# pure_energy.net
KiCad netlist of a schematic drawn in EAGLE
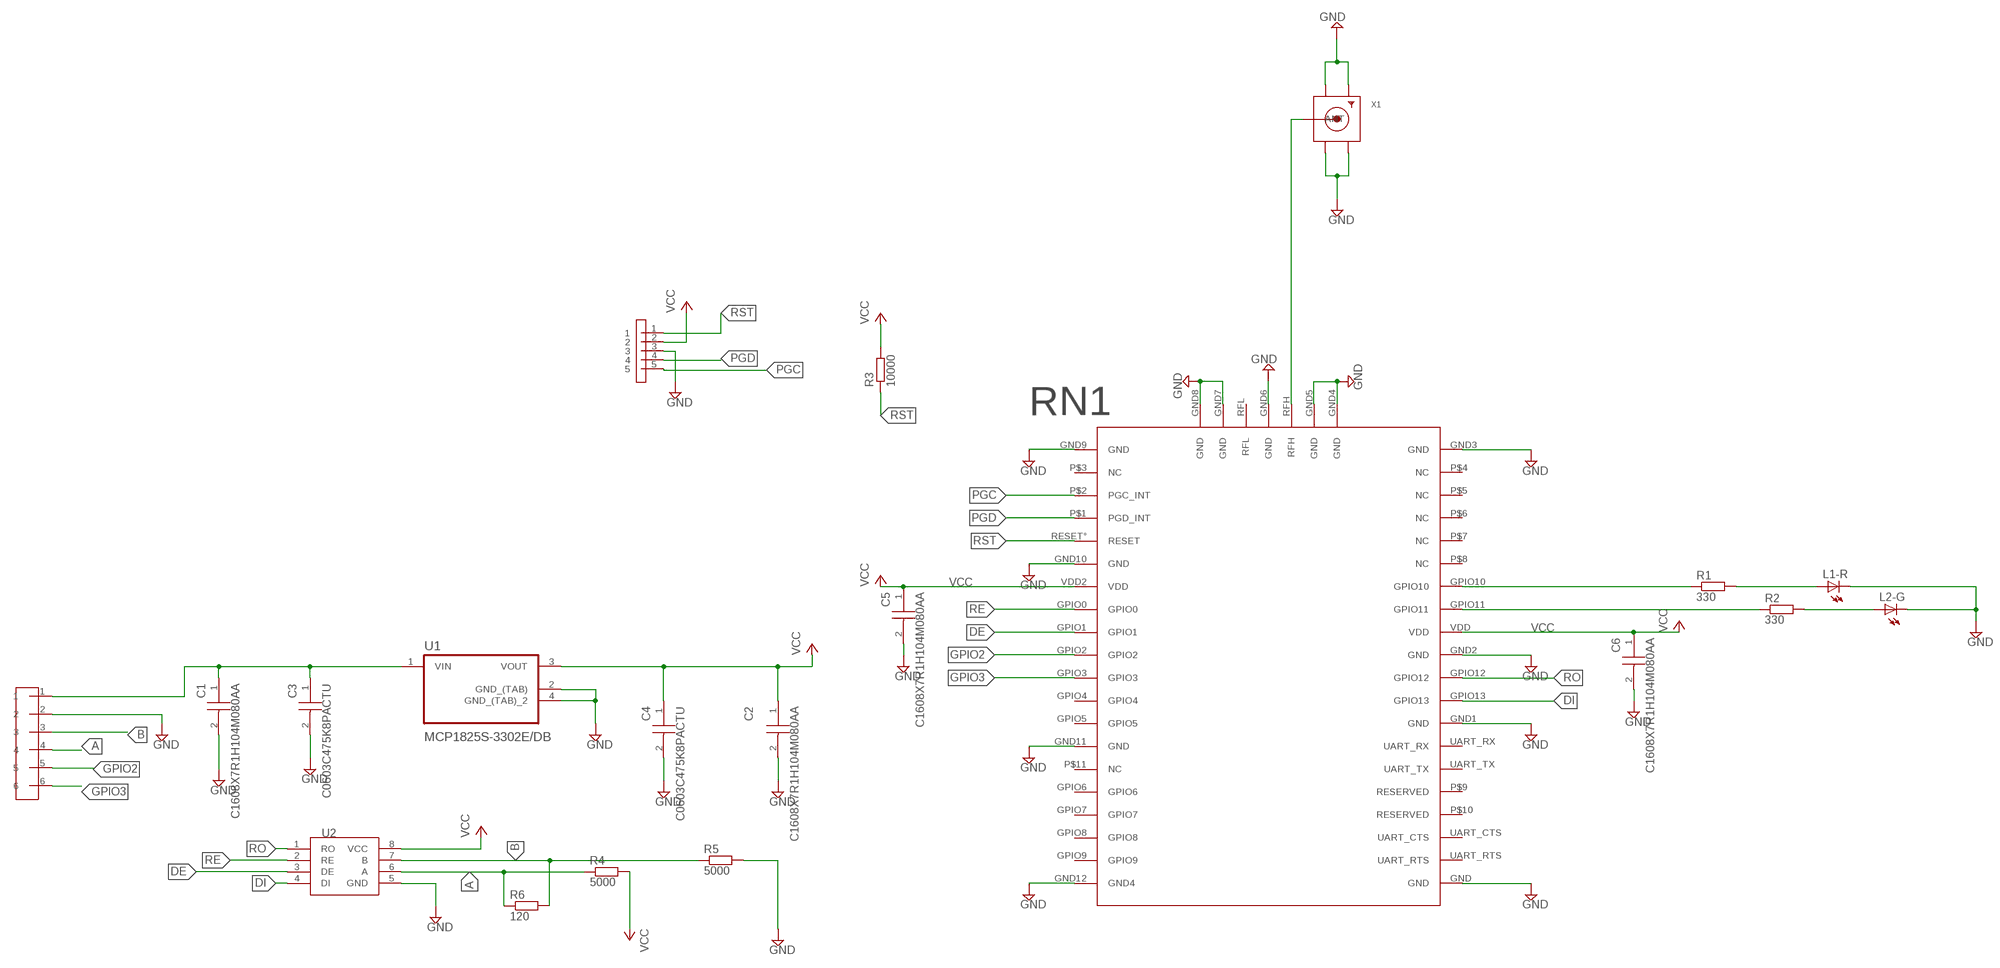
[diagram p0: schematic, sheet 1]

(export (version "E")
  (design (tool "Eeschema 10.0.6"))
  (components
    (comp (ref "C1")
      (value "C1608X7R1H104M080AA")
      (footprint "eagle-import:CAPC1608X80N")
      (fields (field (name "MOUSER_PART_NUMBER") "810-C1608X7R1H104M"))
      (libsource (lib "eagle-import") (part "C1608X7R1H104M080AA"))
    )
    (comp (ref "C2")
      (value "C1608X7R1H104M080AA")
      (footprint "eagle-import:CAPC1608X80N")
      (fields (field (name "MOUSER_PART_NUMBER") "810-C1608X7R1H104M"))
      (libsource (lib "eagle-import") (part "C1608X7R1H104M080AA"))
    )
    (comp (ref "C3")
      (value "C0603C475K8PACTU")
      (footprint "eagle-import:CAPC1608X85N")
      (fields (field (name "MOUSER_PART_NUMBER") "80-C0603C475K8P"))
      (libsource (lib "eagle-import") (part "C0603C475K8PACTU"))
    )
    (comp (ref "C4")
      (value "C0603C475K8PACTU")
      (footprint "eagle-import:CAPC1608X85N")
      (fields (field (name "MOUSER_PART_NUMBER") "80-C0603C475K8P"))
      (libsource (lib "eagle-import") (part "C0603C475K8PACTU"))
    )
    (comp (ref "C5")
      (value "C1608X7R1H104M080AA")
      (footprint "eagle-import:CAPC1608X80N")
      (fields (field (name "MOUSER_PART_NUMBER") "810-C1608X7R1H104M"))
      (libsource (lib "eagle-import") (part "C1608X7R1H104M080AA"))
    )
    (comp (ref "C6")
      (value "C1608X7R1H104M080AA")
      (footprint "eagle-import:CAPC1608X80N")
      (fields (field (name "MOUSER_PART_NUMBER") "810-C1608X7R1H104M"))
      (libsource (lib "eagle-import") (part "C1608X7R1H104M080AA"))
    )
    (comp (ref "L1-R")
      (value "LEDCHIP-LED0603")
      (footprint "eagle-import:CHIP-LED0603")
      (libsource (lib "eagle-import") (part "LEDCHIP-LED0603"))
    )
    (comp (ref "L2-G")
      (value "LEDCHIP-LED0603")
      (footprint "eagle-import:CHIP-LED0603")
      (libsource (lib "eagle-import") (part "LEDCHIP-LED0603"))
    )
    (comp (ref "R1")
      (value "330")
      (footprint "eagle-import:R0603")
      (libsource (lib "eagle-import") (part "R-EU_R0603"))
    )
    (comp (ref "R2")
      (value "330")
      (footprint "eagle-import:R0603")
      (libsource (lib "eagle-import") (part "R-EU_R0603"))
    )
    (comp (ref "R3")
      (value "10000")
      (footprint "eagle-import:R0603")
      (libsource (lib "eagle-import") (part "R-EU_R0603"))
    )
    (comp (ref "R4")
      (value "5000")
      (footprint "eagle-import:R0805")
      (libsource (lib "eagle-import") (part "R-EU_R0805"))
    )
    (comp (ref "R5")
      (value "5000")
      (footprint "eagle-import:R0805")
      (libsource (lib "eagle-import") (part "R-EU_R0805"))
    )
    (comp (ref "R6")
      (value "120")
      (footprint "eagle-import:R0805")
      (libsource (lib "eagle-import") (part "R-EU_R0805"))
    )
    (comp (ref "RN1")
      (value "NEW_RN2483")
      (footprint "eagle-import:NEW_RN2483")
      (libsource (lib "eagle-import") (part "NEW_RN2483"))
    )
    (comp (ref "U$1")
      (value "CONNECTOR6_V2")
      (footprint "eagle-import:CONNECTOR6_V2")
      (libsource (lib "eagle-import") (part "CONNECTOR6_V2"))
    )
    (comp (ref "U$3")
      (value "ICSP_V2")
      (footprint "eagle-import:ICSP_V2")
      (libsource (lib "eagle-import") (part "ICSP_V2"))
    )
    (comp (ref "U1")
      (value "MCP1825S-3302E/DB")
      (footprint "eagle-import:SOT230P700X180-4N")
      (fields (field (name "MF") "Microchip"))
      (libsource (lib "eagle-import") (part "MCP1825S-3302E/DB"))
    )
    (comp (ref "U2")
      (value "AMD3485E")
      (footprint "eagle-import:AMD3485E")
      (libsource (lib "eagle-import") (part "AMD3485E"))
    )
    (comp (ref "X1")
      (value "SMACONNECTOR_EDGE")
      (footprint "eagle-import:SMA_EDGELAUNCH")
      (libsource (lib "eagle-import") (part "SMACONNECTOR_EDGE"))
    )
  )
  (nets
    (net (code "1") (name "A") (class "Default")
      (node (ref "R4") (pin "1") (pinfunction "1_1") (pintype "passive"))
      (node (ref "R6") (pin "1") (pinfunction "1_1") (pintype "passive"))
      (node (ref "U$1") (pin "4") (pinfunction "4_4") (pintype "bidirectional"))
      (node (ref "U2") (pin "6") (pinfunction "A_6") (pintype "bidirectional"))
    )
    (net (code "2") (name "B") (class "Default")
      (node (ref "R5") (pin "1") (pinfunction "1_1") (pintype "passive"))
      (node (ref "R6") (pin "2") (pinfunction "2_2") (pintype "passive"))
      (node (ref "U$1") (pin "3") (pinfunction "3_3") (pintype "bidirectional"))
      (node (ref "U2") (pin "7") (pinfunction "B_7") (pintype "bidirectional"))
    )
    (net (code "3") (name "DE") (class "Default")
      (node (ref "RN1") (pin "GPIO1") (pinfunction "GPIO1_GPIO1") (pintype "bidirectional"))
      (node (ref "U2") (pin "3") (pinfunction "DE_3") (pintype "bidirectional"))
    )
    (net (code "4") (name "DI") (class "Default")
      (node (ref "RN1") (pin "GPIO13") (pinfunction "GPIO13_GPIO13") (pintype "bidirectional"))
      (node (ref "U2") (pin "4") (pinfunction "DI_4") (pintype "bidirectional"))
    )
    (net (code "5") (name "GND") (class "Default")
      (node (ref "C1") (pin "2") (pinfunction "2_2") (pintype "bidirectional"))
      (node (ref "C2") (pin "2") (pinfunction "2_2") (pintype "bidirectional"))
      (node (ref "C3") (pin "2") (pinfunction "C2_2") (pintype "bidirectional"))
      (node (ref "C4") (pin "2") (pinfunction "C2_2") (pintype "bidirectional"))
      (node (ref "C5") (pin "2") (pinfunction "2_2") (pintype "bidirectional"))
      (node (ref "C6") (pin "2") (pinfunction "2_2") (pintype "bidirectional"))
      (node (ref "L1-R") (pin "C") (pinfunction "C_C") (pintype "passive"))
      (node (ref "L2-G") (pin "C") (pinfunction "C_C") (pintype "passive"))
      (node (ref "R5") (pin "2") (pinfunction "2_2") (pintype "passive"))
      (node (ref "RN1") (pin "GND") (pinfunction "GND_GND") (pintype "bidirectional"))
      (node (ref "RN1") (pin "GND1") (pinfunction "GND_GND1") (pintype "bidirectional"))
      (node (ref "RN1") (pin "GND10") (pinfunction "GND_GND10") (pintype "bidirectional"))
      (node (ref "RN1") (pin "GND11") (pinfunction "GND_GND11") (pintype "bidirectional"))
      (node (ref "RN1") (pin "GND12") (pinfunction "GND4_GND12") (pintype "bidirectional"))
      (node (ref "RN1") (pin "GND2") (pinfunction "GND_GND2") (pintype "bidirectional"))
      (node (ref "RN1") (pin "GND3") (pinfunction "GND_GND3") (pintype "bidirectional"))
      (node (ref "RN1") (pin "GND4") (pinfunction "GND_GND4") (pintype "bidirectional"))
      (node (ref "RN1") (pin "GND5") (pinfunction "GND_GND5") (pintype "bidirectional"))
      (node (ref "RN1") (pin "GND6") (pinfunction "GND_GND6") (pintype "bidirectional"))
      (node (ref "RN1") (pin "GND7") (pinfunction "GND_GND7") (pintype "bidirectional"))
      (node (ref "RN1") (pin "GND8") (pinfunction "GND_GND8") (pintype "bidirectional"))
      (node (ref "RN1") (pin "GND9") (pinfunction "GND_GND9") (pintype "bidirectional"))
      (node (ref "U$1") (pin "2") (pinfunction "2_2") (pintype "bidirectional"))
      (node (ref "U$3") (pin "3") (pinfunction "3_3") (pintype "bidirectional"))
      (node (ref "U1") (pin "2") (pinfunction "GND_(TAB)_2") (pintype "power_in"))
      (node (ref "U1") (pin "4") (pinfunction "GND_(TAB)_2_4") (pintype "power_in"))
      (node (ref "U2") (pin "5") (pinfunction "GND_5") (pintype "bidirectional"))
      (node (ref "X1") (pin "GND@1") (pinfunction "GND4_GND@1") (pintype "power_in"))
      (node (ref "X1") (pin "GND@2") (pinfunction "GND3_GND@2") (pintype "power_in"))
      (node (ref "X1") (pin "GND@3") (pinfunction "GND2_GND@3") (pintype "power_in"))
      (node (ref "X1") (pin "GND@4") (pinfunction "GND1_GND@4") (pintype "power_in"))
    )
    (net (code "6") (name "GPIO2") (class "Default")
      (node (ref "RN1") (pin "GPIO2") (pinfunction "GPIO2_GPIO2") (pintype "bidirectional"))
      (node (ref "U$1") (pin "5") (pinfunction "5_5") (pintype "bidirectional"))
    )
    (net (code "7") (name "GPIO3") (class "Default")
      (node (ref "RN1") (pin "GPIO3") (pinfunction "GPIO3_GPIO3") (pintype "bidirectional"))
      (node (ref "U$1") (pin "6") (pinfunction "6_6") (pintype "bidirectional"))
    )
    (net (code "8") (name "Net-(C3-C1)") (class "Default")
      (node (ref "C1") (pin "1") (pinfunction "1_1") (pintype "bidirectional"))
      (node (ref "C3") (pin "1") (pinfunction "C1_1") (pintype "bidirectional"))
      (node (ref "U$1") (pin "1") (pinfunction "1_1") (pintype "bidirectional"))
      (node (ref "U1") (pin "1") (pinfunction "VIN_1") (pintype "input"))
    )
    (net (code "9") (name "Net-(L1-R-PadA)") (class "Default")
      (node (ref "L1-R") (pin "A") (pinfunction "A_A") (pintype "passive"))
      (node (ref "R1") (pin "2") (pinfunction "2_2") (pintype "passive"))
    )
    (net (code "10") (name "Net-(L2-G-PadA)") (class "Default")
      (node (ref "L2-G") (pin "A") (pinfunction "A_A") (pintype "passive"))
      (node (ref "R2") (pin "2") (pinfunction "2_2") (pintype "passive"))
    )
    (net (code "11") (name "Net-(R1-Pad1)") (class "Default")
      (node (ref "R1") (pin "1") (pinfunction "1_1") (pintype "passive"))
      (node (ref "RN1") (pin "GPIO10") (pinfunction "GPIO10_GPIO10") (pintype "bidirectional"))
    )
    (net (code "12") (name "Net-(R2-Pad1)") (class "Default")
      (node (ref "R2") (pin "1") (pinfunction "1_1") (pintype "passive"))
      (node (ref "RN1") (pin "GPIO11") (pinfunction "GPIO11_GPIO11") (pintype "bidirectional"))
    )
    (net (code "13") (name "Net-(X1-ANT)") (class "Default")
      (node (ref "RN1") (pin "RFH") (pinfunction "RFH_RFH") (pintype "bidirectional"))
      (node (ref "X1") (pin "P") (pinfunction "ANT_P") (pintype "bidirectional"))
    )
    (net (code "14") (name "PGC") (class "Default")
      (node (ref "RN1") (pin "P$2") (pinfunction "PGC_INT_P$2") (pintype "bidirectional"))
      (node (ref "U$3") (pin "5") (pinfunction "5_5") (pintype "bidirectional"))
    )
    (net (code "15") (name "PGD") (class "Default")
      (node (ref "RN1") (pin "P$1") (pinfunction "PGD_INT_P$1") (pintype "bidirectional"))
      (node (ref "U$3") (pin "4") (pinfunction "4_4") (pintype "bidirectional"))
    )
    (net (code "16") (name "RE") (class "Default")
      (node (ref "RN1") (pin "GPIO0") (pinfunction "GPIO0_GPIO0") (pintype "bidirectional"))
      (node (ref "U2") (pin "2") (pinfunction "RE_2") (pintype "bidirectional"))
    )
    (net (code "17") (name "RO") (class "Default")
      (node (ref "RN1") (pin "GPIO12") (pinfunction "GPIO12_GPIO12") (pintype "bidirectional"))
      (node (ref "U2") (pin "1") (pinfunction "RO_1") (pintype "bidirectional"))
    )
    (net (code "18") (name "RST") (class "Default")
      (node (ref "R3") (pin "1") (pinfunction "1_1") (pintype "passive"))
      (node (ref "RN1") (pin "RESET°") (pinfunction "RESET_RESET°") (pintype "bidirectional"))
      (node (ref "U$3") (pin "1") (pinfunction "1_1") (pintype "bidirectional"))
    )
    (net (code "19") (name "VCC") (class "Default")
      (node (ref "C2") (pin "1") (pinfunction "1_1") (pintype "bidirectional"))
      (node (ref "C4") (pin "1") (pinfunction "C1_1") (pintype "bidirectional"))
      (node (ref "C5") (pin "1") (pinfunction "1_1") (pintype "bidirectional"))
      (node (ref "C6") (pin "1") (pinfunction "1_1") (pintype "bidirectional"))
      (node (ref "R3") (pin "2") (pinfunction "2_2") (pintype "passive"))
      (node (ref "R4") (pin "2") (pinfunction "2_2") (pintype "passive"))
      (node (ref "RN1") (pin "VDD") (pinfunction "VDD_VDD") (pintype "bidirectional"))
      (node (ref "RN1") (pin "VDD2") (pinfunction "VDD_VDD2") (pintype "bidirectional"))
      (node (ref "U$3") (pin "2") (pinfunction "2_2") (pintype "bidirectional"))
      (node (ref "U1") (pin "3") (pinfunction "VOUT_3") (pintype "output"))
      (node (ref "U2") (pin "8") (pinfunction "VCC_8") (pintype "bidirectional"))
    )
    (net (code "20") (name "unconnected-(RN1-NC-PadP$3)") (class "Default")
      (node (ref "RN1") (pin "P$3") (pinfunction "NC_P$3") (pintype "bidirectional"))
    )
    (net (code "21") (name "unconnected-(RN1-NC-PadP$4)") (class "Default")
      (node (ref "RN1") (pin "P$4") (pinfunction "NC_P$4") (pintype "bidirectional"))
    )
    (net (code "22") (name "unconnected-(RN1-NC-PadP$5)") (class "Default")
      (node (ref "RN1") (pin "P$5") (pinfunction "NC_P$5") (pintype "bidirectional"))
    )
    (net (code "23") (name "unconnected-(RN1-NC-PadP$6)") (class "Default")
      (node (ref "RN1") (pin "P$6") (pinfunction "NC_P$6") (pintype "bidirectional"))
    )
    (net (code "24") (name "unconnected-(RN1-NC-PadP$7)") (class "Default")
      (node (ref "RN1") (pin "P$7") (pinfunction "NC_P$7") (pintype "bidirectional"))
    )
    (net (code "25") (name "unconnected-(RN1-NC-PadP$8)") (class "Default")
      (node (ref "RN1") (pin "P$8") (pinfunction "NC_P$8") (pintype "bidirectional"))
    )
    (net (code "26") (name "unconnected-(RN1-NC-PadP$11)") (class "Default")
      (node (ref "RN1") (pin "P$11") (pinfunction "NC_P$11") (pintype "bidirectional"))
    )
    (net (code "27") (name "unconnected-(RN1-PadGPIO4)") (class "Default")
      (node (ref "RN1") (pin "GPIO4") (pinfunction "GPIO4_GPIO4") (pintype "bidirectional"))
    )
    (net (code "28") (name "unconnected-(RN1-PadGPIO5)") (class "Default")
      (node (ref "RN1") (pin "GPIO5") (pinfunction "GPIO5_GPIO5") (pintype "bidirectional"))
    )
    (net (code "29") (name "unconnected-(RN1-PadGPIO6)") (class "Default")
      (node (ref "RN1") (pin "GPIO6") (pinfunction "GPIO6_GPIO6") (pintype "bidirectional"))
    )
    (net (code "30") (name "unconnected-(RN1-PadGPIO7)") (class "Default")
      (node (ref "RN1") (pin "GPIO7") (pinfunction "GPIO7_GPIO7") (pintype "bidirectional"))
    )
    (net (code "31") (name "unconnected-(RN1-PadGPIO8)") (class "Default")
      (node (ref "RN1") (pin "GPIO8") (pinfunction "GPIO8_GPIO8") (pintype "bidirectional"))
    )
    (net (code "32") (name "unconnected-(RN1-PadGPIO9)") (class "Default")
      (node (ref "RN1") (pin "GPIO9") (pinfunction "GPIO9_GPIO9") (pintype "bidirectional"))
    )
    (net (code "33") (name "unconnected-(RN1-PadRFL)") (class "Default")
      (node (ref "RN1") (pin "RFL") (pinfunction "RFL_RFL") (pintype "bidirectional"))
    )
    (net (code "34") (name "unconnected-(RN1-PadUART_CTS)") (class "Default")
      (node (ref "RN1") (pin "UART_CTS") (pinfunction "UART_CTS_UART_CTS") (pintype "bidirectional"))
    )
    (net (code "35") (name "unconnected-(RN1-PadUART_RTS)") (class "Default")
      (node (ref "RN1") (pin "UART_RTS") (pinfunction "UART_RTS_UART_RTS") (pintype "bidirectional"))
    )
    (net (code "36") (name "unconnected-(RN1-PadUART_RX)") (class "Default")
      (node (ref "RN1") (pin "UART_RX") (pinfunction "UART_RX_UART_RX") (pintype "bidirectional"))
    )
    (net (code "37") (name "unconnected-(RN1-PadUART_TX)") (class "Default")
      (node (ref "RN1") (pin "UART_TX") (pinfunction "UART_TX_UART_TX") (pintype "bidirectional"))
    )
    (net (code "38") (name "unconnected-(RN1-RESERVED-PadP$9)") (class "Default")
      (node (ref "RN1") (pin "P$9") (pinfunction "RESERVED_P$9") (pintype "bidirectional"))
    )
    (net (code "39") (name "unconnected-(RN1-RESERVED-PadP$10)") (class "Default")
      (node (ref "RN1") (pin "P$10") (pinfunction "RESERVED_P$10") (pintype "bidirectional"))
    )
  )
)
